# color_sensor.net
KiCad netlist of a schematic drawn in EAGLE
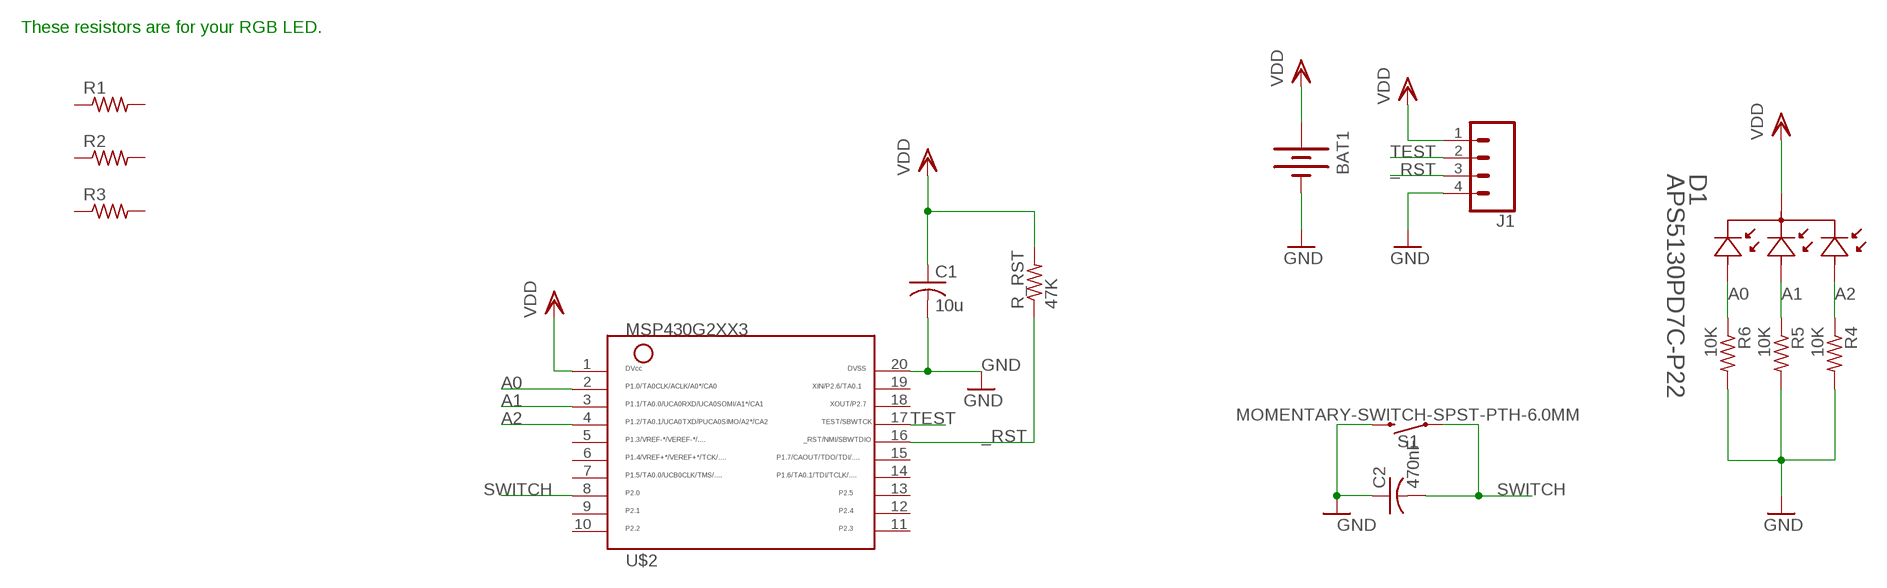
[diagram p0: schematic, sheet 1]

(export (version "E")
  (design (tool "Eeschema 10.0.6"))
  (components
    (comp (ref "BAT1")
      (value "BATTERYBU2032SM")
      (footprint "eagle-import:BU2032SM")
      (libsource (lib "eagle-import") (part "BATTERYBU2032SM"))
    )
    (comp (ref "C1")
      (value "10u")
      (footprint "eagle-import:C1206")
      (libsource (lib "eagle-import") (part "C-USC1206"))
    )
    (comp (ref "C2")
      (value "470nF")
      (footprint "eagle-import:C1206")
      (libsource (lib "eagle-import") (part "C-USC1206"))
    )
    (comp (ref "D1")
      (value "APS5130PD7C-P22")
      (footprint "eagle-import:LED_APS5130PD7C-P22_KNB")
      (libsource (lib "eagle-import") (part "APS5130PD7C-P22"))
    )
    (comp (ref "J1")
      (value "CONN_04LOCK")
      (footprint "eagle-import:1X04_LOCK")
      (libsource (lib "eagle-import") (part "CONN_04LOCK"))
    )
    (comp (ref "R1")
      (value "R-US_R1206")
      (footprint "eagle-import:R1206")
      (libsource (lib "eagle-import") (part "R-US_R1206"))
    )
    (comp (ref "R2")
      (value "R-US_R1206")
      (footprint "eagle-import:R1206")
      (libsource (lib "eagle-import") (part "R-US_R1206"))
    )
    (comp (ref "R3")
      (value "R-US_R1206")
      (footprint "eagle-import:R1206")
      (libsource (lib "eagle-import") (part "R-US_R1206"))
    )
    (comp (ref "R4")
      (value "10K")
      (footprint "eagle-import:R1206")
      (libsource (lib "eagle-import") (part "R-US_R1206"))
    )
    (comp (ref "R5")
      (value "10K")
      (footprint "eagle-import:R1206")
      (libsource (lib "eagle-import") (part "R-US_R1206"))
    )
    (comp (ref "R6")
      (value "10K")
      (footprint "eagle-import:R1206")
      (libsource (lib "eagle-import") (part "R-US_R1206"))
    )
    (comp (ref "R_RST")
      (value "47K")
      (footprint "eagle-import:R1206")
      (libsource (lib "eagle-import") (part "R-US_R1206"))
    )
    (comp (ref "S1")
      (value "MOMENTARY-SWITCH-SPST-PTH-6.0MM")
      (footprint "eagle-import:TACTILE_SWITCH_PTH_6.0MM")
      (libsource (lib "eagle-import") (part "MOMENTARY-SWITCH-SPST-PTH-6.0MM"))
    )
    (comp (ref "U$2")
      (value "MSP430G2XX3TSSOP")
      (footprint "eagle-import:PW20")
      (libsource (lib "eagle-import") (part "MSP430G2XX3TSSOP"))
    )
  )
  (nets
    (net (code "1") (name "/A0") (class "Default")
      (node (ref "D1") (pin "3") (pinfunction "3_3") (pintype "passive"))
      (node (ref "R6") (pin "1") (pinfunction "1_1") (pintype "passive"))
      (node (ref "U$2") (pin "2") (pinfunction "2_2") (pintype "bidirectional"))
    )
    (net (code "2") (name "/A1") (class "Default")
      (node (ref "D1") (pin "2") (pinfunction "2_2") (pintype "passive"))
      (node (ref "R5") (pin "1") (pinfunction "1_1") (pintype "passive"))
      (node (ref "U$2") (pin "3") (pinfunction "3_3") (pintype "bidirectional"))
    )
    (net (code "3") (name "/A2") (class "Default")
      (node (ref "D1") (pin "1") (pinfunction "1_1") (pintype "passive"))
      (node (ref "R4") (pin "1") (pinfunction "1_1") (pintype "passive"))
      (node (ref "U$2") (pin "4") (pinfunction "4_4") (pintype "bidirectional"))
    )
    (net (code "4") (name "/SWITCH") (class "Default")
      (node (ref "C2") (pin "2") (pinfunction "2_2") (pintype "passive"))
      (node (ref "S1") (pin "1") (pinfunction "1_1") (pintype "passive"))
      (node (ref "U$2") (pin "8") (pinfunction "8_8") (pintype "bidirectional"))
    )
    (net (code "5") (name "/TEST") (class "Default")
      (node (ref "J1") (pin "2") (pinfunction "2_2") (pintype "passive"))
      (node (ref "U$2") (pin "17") (pinfunction "17_17") (pintype "bidirectional"))
    )
    (net (code "6") (name "/_RST") (class "Default")
      (node (ref "J1") (pin "3") (pinfunction "3_3") (pintype "passive"))
      (node (ref "R_RST") (pin "1") (pinfunction "1_1") (pintype "passive"))
      (node (ref "U$2") (pin "16") (pinfunction "16_16") (pintype "bidirectional"))
    )
    (net (code "7") (name "GND") (class "Default")
      (node (ref "BAT1") (pin "P$2") (pinfunction "-_P$2") (pintype "power_in"))
      (node (ref "C1") (pin "2") (pinfunction "2_2") (pintype "passive"))
      (node (ref "C2") (pin "1") (pinfunction "1_1") (pintype "passive"))
      (node (ref "J1") (pin "4") (pinfunction "4_4") (pintype "passive"))
      (node (ref "R4") (pin "2") (pinfunction "2_2") (pintype "passive"))
      (node (ref "R5") (pin "2") (pinfunction "2_2") (pintype "passive"))
      (node (ref "R6") (pin "2") (pinfunction "2_2") (pintype "passive"))
      (node (ref "S1") (pin "3") (pinfunction "2_3") (pintype "passive"))
      (node (ref "U$2") (pin "20") (pinfunction "20_20") (pintype "bidirectional"))
    )
    (net (code "8") (name "VDD") (class "Default")
      (node (ref "BAT1") (pin "P$1") (pinfunction "+_P$1") (pintype "power_in"))
      (node (ref "C1") (pin "1") (pinfunction "1_1") (pintype "passive"))
      (node (ref "D1") (pin "4") (pinfunction "4_4") (pintype "passive"))
      (node (ref "J1") (pin "1") (pinfunction "1_1") (pintype "passive"))
      (node (ref "R_RST") (pin "2") (pinfunction "2_2") (pintype "passive"))
      (node (ref "U$2") (pin "1") (pinfunction "1_1") (pintype "bidirectional"))
    )
    (net (code "9") (name "unconnected-(R1-Pad1)") (class "Default")
      (node (ref "R1") (pin "1") (pinfunction "1_1") (pintype "passive"))
    )
    (net (code "10") (name "unconnected-(R1-Pad2)") (class "Default")
      (node (ref "R1") (pin "2") (pinfunction "2_2") (pintype "passive"))
    )
    (net (code "11") (name "unconnected-(R2-Pad1)") (class "Default")
      (node (ref "R2") (pin "1") (pinfunction "1_1") (pintype "passive"))
    )
    (net (code "12") (name "unconnected-(R2-Pad2)") (class "Default")
      (node (ref "R2") (pin "2") (pinfunction "2_2") (pintype "passive"))
    )
    (net (code "13") (name "unconnected-(R3-Pad1)") (class "Default")
      (node (ref "R3") (pin "1") (pinfunction "1_1") (pintype "passive"))
    )
    (net (code "14") (name "unconnected-(R3-Pad2)") (class "Default")
      (node (ref "R3") (pin "2") (pinfunction "2_2") (pintype "passive"))
    )
    (net (code "15") (name "unconnected-(U$2-Pad5)") (class "Default")
      (node (ref "U$2") (pin "5") (pinfunction "5_5") (pintype "bidirectional"))
    )
    (net (code "16") (name "unconnected-(U$2-Pad6)") (class "Default")
      (node (ref "U$2") (pin "6") (pinfunction "6_6") (pintype "bidirectional"))
    )
    (net (code "17") (name "unconnected-(U$2-Pad7)") (class "Default")
      (node (ref "U$2") (pin "7") (pinfunction "7_7") (pintype "bidirectional"))
    )
    (net (code "18") (name "unconnected-(U$2-Pad9)") (class "Default")
      (node (ref "U$2") (pin "9") (pinfunction "9_9") (pintype "bidirectional"))
    )
    (net (code "19") (name "unconnected-(U$2-Pad10)") (class "Default")
      (node (ref "U$2") (pin "10") (pinfunction "10_10") (pintype "bidirectional"))
    )
    (net (code "20") (name "unconnected-(U$2-Pad11)") (class "Default")
      (node (ref "U$2") (pin "11") (pinfunction "11_11") (pintype "bidirectional"))
    )
    (net (code "21") (name "unconnected-(U$2-Pad12)") (class "Default")
      (node (ref "U$2") (pin "12") (pinfunction "12_12") (pintype "bidirectional"))
    )
    (net (code "22") (name "unconnected-(U$2-Pad13)") (class "Default")
      (node (ref "U$2") (pin "13") (pinfunction "13_13") (pintype "bidirectional"))
    )
    (net (code "23") (name "unconnected-(U$2-Pad14)") (class "Default")
      (node (ref "U$2") (pin "14") (pinfunction "14_14") (pintype "bidirectional"))
    )
    (net (code "24") (name "unconnected-(U$2-Pad15)") (class "Default")
      (node (ref "U$2") (pin "15") (pinfunction "15_15") (pintype "bidirectional"))
    )
    (net (code "25") (name "unconnected-(U$2-Pad18)") (class "Default")
      (node (ref "U$2") (pin "18") (pinfunction "18_18") (pintype "bidirectional"))
    )
    (net (code "26") (name "unconnected-(U$2-Pad19)") (class "Default")
      (node (ref "U$2") (pin "19") (pinfunction "19_19") (pintype "bidirectional"))
    )
  )
)
